# B135X.net
KiCad netlist of a schematic drawn in EAGLE
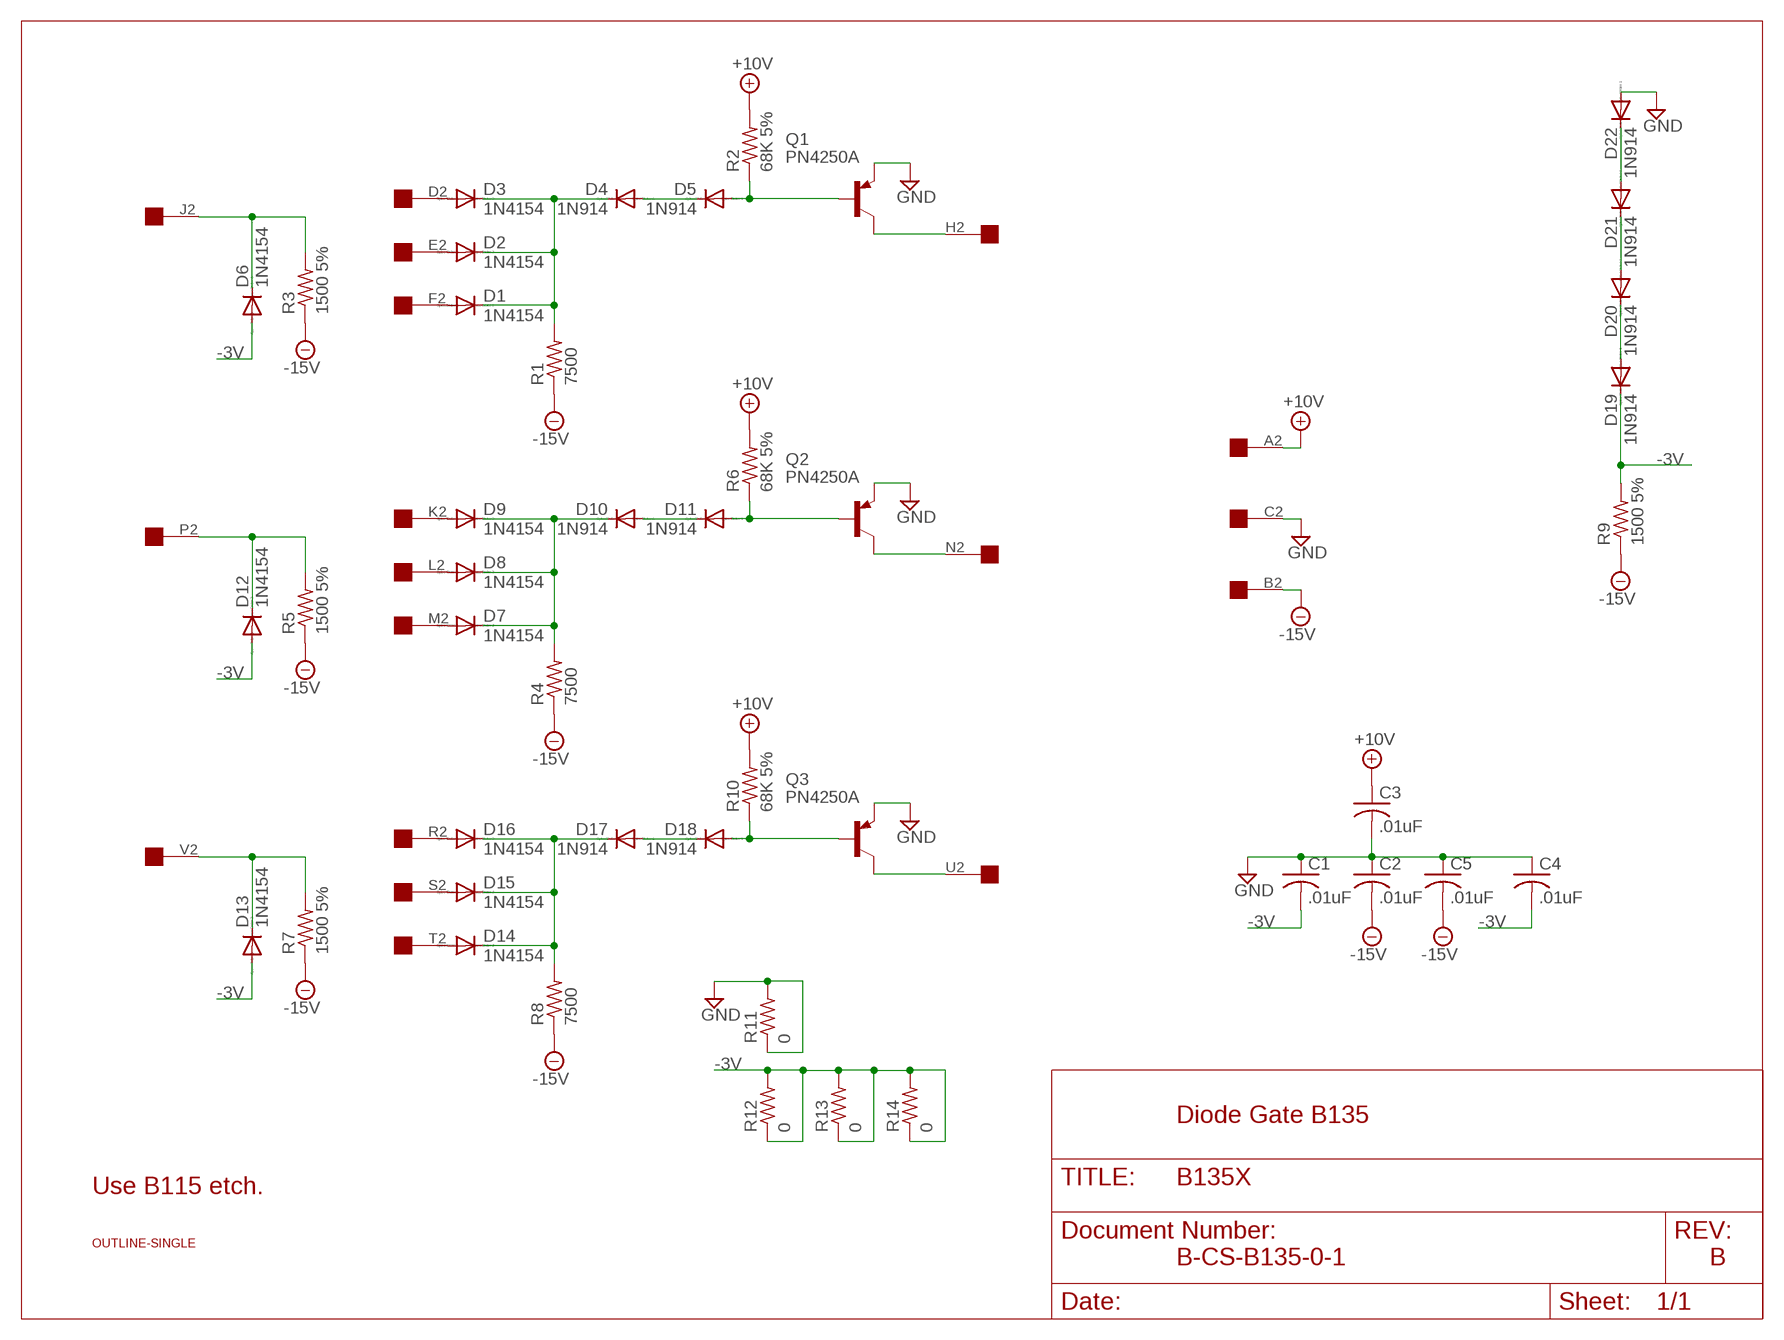
[diagram p0: schematic, sheet 1]

(export (version "E")
  (design (tool "Eeschema 10.0.6"))
  (components
    (comp (ref "C1")
      (value ".01uF")
      (footprint "eagle-import:C063-025X075")
      (libsource (lib "eagle-import") (part "C-US"))
    )
    (comp (ref "C2")
      (value ".01uF")
      (footprint "eagle-import:C063-025X075")
      (libsource (lib "eagle-import") (part "C-US"))
    )
    (comp (ref "C3")
      (value ".01uF")
      (footprint "eagle-import:C063-025X075")
      (libsource (lib "eagle-import") (part "C-US"))
    )
    (comp (ref "C4")
      (value ".01uF")
      (footprint "eagle-import:C063-025X075")
      (libsource (lib "eagle-import") (part "C-US"))
    )
    (comp (ref "C5")
      (value ".01uF")
      (footprint "eagle-import:C063-025X075")
      (libsource (lib "eagle-import") (part "C-US"))
    )
    (comp (ref "D1")
      (value "1N4154")
      (footprint "eagle-import:DO35-10")
      (libsource (lib "eagle-import") (part "DIODE-DO35-10"))
    )
    (comp (ref "D2")
      (value "1N4154")
      (footprint "eagle-import:DO35-10")
      (libsource (lib "eagle-import") (part "DIODE-DO35-10"))
    )
    (comp (ref "D3")
      (value "1N4154")
      (footprint "eagle-import:DO35-10")
      (libsource (lib "eagle-import") (part "DIODE-DO35-10"))
    )
    (comp (ref "D4")
      (value "1N914")
      (footprint "eagle-import:DO35-10")
      (libsource (lib "eagle-import") (part "DIODE-DO35-10"))
    )
    (comp (ref "D5")
      (value "1N914")
      (footprint "eagle-import:DO35-10")
      (libsource (lib "eagle-import") (part "DIODE-DO35-10"))
    )
    (comp (ref "D6")
      (value "1N4154")
      (footprint "eagle-import:DO35-10")
      (libsource (lib "eagle-import") (part "DIODE-DO35-10"))
    )
    (comp (ref "D7")
      (value "1N4154")
      (footprint "eagle-import:DO35-10")
      (libsource (lib "eagle-import") (part "DIODE-DO35-10"))
    )
    (comp (ref "D8")
      (value "1N4154")
      (footprint "eagle-import:DO35-10")
      (libsource (lib "eagle-import") (part "DIODE-DO35-10"))
    )
    (comp (ref "D9")
      (value "1N4154")
      (footprint "eagle-import:DO35-10")
      (libsource (lib "eagle-import") (part "DIODE-DO35-10"))
    )
    (comp (ref "D10")
      (value "1N914")
      (footprint "eagle-import:DO35-10")
      (libsource (lib "eagle-import") (part "DIODE-DO35-10"))
    )
    (comp (ref "D11")
      (value "1N914")
      (footprint "eagle-import:DO35-10")
      (libsource (lib "eagle-import") (part "DIODE-DO35-10"))
    )
    (comp (ref "D12")
      (value "1N4154")
      (footprint "eagle-import:DO35-10")
      (libsource (lib "eagle-import") (part "DIODE-DO35-10"))
    )
    (comp (ref "D13")
      (value "1N4154")
      (footprint "eagle-import:DO35-10")
      (libsource (lib "eagle-import") (part "DIODE-DO35-10"))
    )
    (comp (ref "D14")
      (value "1N4154")
      (footprint "eagle-import:DO35-10")
      (libsource (lib "eagle-import") (part "DIODE-DO35-10"))
    )
    (comp (ref "D15")
      (value "1N4154")
      (footprint "eagle-import:DO35-10")
      (libsource (lib "eagle-import") (part "DIODE-DO35-10"))
    )
    (comp (ref "D16")
      (value "1N4154")
      (footprint "eagle-import:DO35-10")
      (libsource (lib "eagle-import") (part "DIODE-DO35-10"))
    )
    (comp (ref "D17")
      (value "1N914")
      (footprint "eagle-import:DO35-10")
      (libsource (lib "eagle-import") (part "DIODE-DO35-10"))
    )
    (comp (ref "D18")
      (value "1N914")
      (footprint "eagle-import:DO35-10")
      (libsource (lib "eagle-import") (part "DIODE-DO35-10"))
    )
    (comp (ref "D19")
      (value "1N914")
      (footprint "eagle-import:DO35-10")
      (libsource (lib "eagle-import") (part "DIODE-DO35-10"))
    )
    (comp (ref "D20")
      (value "1N914")
      (footprint "eagle-import:DO35-10")
      (libsource (lib "eagle-import") (part "DIODE-DO35-10"))
    )
    (comp (ref "D21")
      (value "1N914")
      (footprint "eagle-import:DO35-10")
      (libsource (lib "eagle-import") (part "DIODE-DO35-10"))
    )
    (comp (ref "D22")
      (value "1N914")
      (footprint "eagle-import:DO35-10")
      (libsource (lib "eagle-import") (part "DIODE-DO35-10"))
    )
    (comp (ref "Q1")
      (value "PN4250A")
      (footprint "eagle-import:TO5")
      (libsource (lib "eagle-import") (part "-PNP-TO5"))
    )
    (comp (ref "Q2")
      (value "PN4250A")
      (footprint "eagle-import:TO5")
      (libsource (lib "eagle-import") (part "-PNP-TO5"))
    )
    (comp (ref "Q3")
      (value "PN4250A")
      (footprint "eagle-import:TO5")
      (libsource (lib "eagle-import") (part "-PNP-TO5"))
    )
    (comp (ref "R1")
      (value "7500")
      (footprint "eagle-import:0207_10")
      (libsource (lib "eagle-import") (part "R-US_0207/10"))
    )
    (comp (ref "R2")
      (value "68K 5%")
      (footprint "eagle-import:0207_10")
      (libsource (lib "eagle-import") (part "R-US_0207/10"))
    )
    (comp (ref "R3")
      (value "1500 5%")
      (footprint "eagle-import:0207_10")
      (libsource (lib "eagle-import") (part "R-US_0207/10"))
    )
    (comp (ref "R4")
      (value "7500")
      (footprint "eagle-import:0207_10")
      (libsource (lib "eagle-import") (part "R-US_0207/10"))
    )
    (comp (ref "R5")
      (value "1500 5%")
      (footprint "eagle-import:0207_10")
      (libsource (lib "eagle-import") (part "R-US_0207/10"))
    )
    (comp (ref "R6")
      (value "68K 5%")
      (footprint "eagle-import:0207_10")
      (libsource (lib "eagle-import") (part "R-US_0207/10"))
    )
    (comp (ref "R7")
      (value "1500 5%")
      (footprint "eagle-import:0207_10")
      (libsource (lib "eagle-import") (part "R-US_0207/10"))
    )
    (comp (ref "R8")
      (value "7500")
      (footprint "eagle-import:0207_10")
      (libsource (lib "eagle-import") (part "R-US_0207/10"))
    )
    (comp (ref "R9")
      (value "1500 5%")
      (footprint "eagle-import:0207_10")
      (libsource (lib "eagle-import") (part "R-US_0207/10"))
    )
    (comp (ref "R10")
      (value "68K 5%")
      (footprint "eagle-import:0207_10")
      (libsource (lib "eagle-import") (part "R-US_0207/10"))
    )
    (comp (ref "R11")
      (value "0")
      (footprint "eagle-import:0207_10")
      (libsource (lib "eagle-import") (part "R-US_0207/10"))
    )
    (comp (ref "R12")
      (value "0")
      (footprint "eagle-import:0207_10")
      (libsource (lib "eagle-import") (part "R-US_0207/10"))
    )
    (comp (ref "R13")
      (value "0")
      (footprint "eagle-import:0207_10")
      (libsource (lib "eagle-import") (part "R-US_0207/10"))
    )
    (comp (ref "R14")
      (value "0")
      (footprint "eagle-import:0207_10")
      (libsource (lib "eagle-import") (part "R-US_0207/10"))
    )
    (comp (ref "U$1")
      (value "OUTLINE-SINGLE")
      (footprint "eagle-import:SINGLE")
      (libsource (lib "eagle-import") (part "OUTLINE-SINGLE"))
    )
    (comp (ref "U$2")
      (value "EDGE-1")
      (footprint "eagle-import:EDGE-CON1")
      (libsource (lib "eagle-import") (part "EDGE-1"))
    )
  )
  (nets
    (net (code "1") (name "+10V") (class "Default")
      (node (ref "C3") (pin "1") (pinfunction "1_1") (pintype "passive"))
      (node (ref "R10") (pin "2") (pinfunction "2_2") (pintype "passive"))
      (node (ref "R2") (pin "2") (pinfunction "2_2") (pintype "passive"))
      (node (ref "R6") (pin "2") (pinfunction "2_2") (pintype "passive"))
      (node (ref "U$2") (pin "A2") (pinfunction "1_A2") (pintype "bidirectional"))
    )
    (net (code "2") (name "-15V") (class "Default")
      (node (ref "C2") (pin "2") (pinfunction "2_2") (pintype "passive"))
      (node (ref "C5") (pin "2") (pinfunction "2_2") (pintype "passive"))
      (node (ref "R1") (pin "1") (pinfunction "1_1") (pintype "passive"))
      (node (ref "R3") (pin "1") (pinfunction "1_1") (pintype "passive"))
      (node (ref "R4") (pin "1") (pinfunction "1_1") (pintype "passive"))
      (node (ref "R5") (pin "1") (pinfunction "1_1") (pintype "passive"))
      (node (ref "R7") (pin "1") (pinfunction "1_1") (pintype "passive"))
      (node (ref "R8") (pin "1") (pinfunction "1_1") (pintype "passive"))
      (node (ref "R9") (pin "1") (pinfunction "1_1") (pintype "passive"))
      (node (ref "U$2") (pin "B2") (pinfunction "1_B2") (pintype "bidirectional"))
    )
    (net (code "3") (name "/-3V") (class "Default")
      (node (ref "C1") (pin "2") (pinfunction "2_2") (pintype "passive"))
      (node (ref "C4") (pin "2") (pinfunction "2_2") (pintype "passive"))
      (node (ref "D12") (pin "A") (pinfunction "A_A") (pintype "passive"))
      (node (ref "D13") (pin "A") (pinfunction "A_A") (pintype "passive"))
      (node (ref "D19") (pin "C") (pinfunction "C_C") (pintype "passive"))
      (node (ref "D6") (pin "A") (pinfunction "A_A") (pintype "passive"))
      (node (ref "R12") (pin "1") (pinfunction "1_1") (pintype "passive"))
      (node (ref "R12") (pin "2") (pinfunction "2_2") (pintype "passive"))
      (node (ref "R13") (pin "1") (pinfunction "1_1") (pintype "passive"))
      (node (ref "R13") (pin "2") (pinfunction "2_2") (pintype "passive"))
      (node (ref "R14") (pin "1") (pinfunction "1_1") (pintype "passive"))
      (node (ref "R14") (pin "2") (pinfunction "2_2") (pintype "passive"))
      (node (ref "R9") (pin "2") (pinfunction "2_2") (pintype "passive"))
    )
    (net (code "4") (name "GND") (class "Default")
      (node (ref "C1") (pin "1") (pinfunction "1_1") (pintype "passive"))
      (node (ref "C2") (pin "1") (pinfunction "1_1") (pintype "passive"))
      (node (ref "C3") (pin "2") (pinfunction "2_2") (pintype "passive"))
      (node (ref "C4") (pin "1") (pinfunction "1_1") (pintype "passive"))
      (node (ref "C5") (pin "1") (pinfunction "1_1") (pintype "passive"))
      (node (ref "D22") (pin "A") (pinfunction "A_A") (pintype "passive"))
      (node (ref "Q1") (pin "1") (pinfunction "E_1") (pintype "passive"))
      (node (ref "Q2") (pin "1") (pinfunction "E_1") (pintype "passive"))
      (node (ref "Q3") (pin "1") (pinfunction "E_1") (pintype "passive"))
      (node (ref "R11") (pin "1") (pinfunction "1_1") (pintype "passive"))
      (node (ref "R11") (pin "2") (pinfunction "2_2") (pintype "passive"))
      (node (ref "U$2") (pin "C2") (pinfunction "1_C2") (pintype "bidirectional"))
    )
    (net (code "5") (name "Net-(D1-PadC)") (class "Default")
      (node (ref "D1") (pin "C") (pinfunction "C_C") (pintype "passive"))
      (node (ref "D2") (pin "C") (pinfunction "C_C") (pintype "passive"))
      (node (ref "D3") (pin "C") (pinfunction "C_C") (pintype "passive"))
      (node (ref "D4") (pin "C") (pinfunction "C_C") (pintype "passive"))
      (node (ref "R1") (pin "2") (pinfunction "2_2") (pintype "passive"))
    )
    (net (code "6") (name "Net-(D4-PadA)") (class "Default")
      (node (ref "D4") (pin "A") (pinfunction "A_A") (pintype "passive"))
      (node (ref "D5") (pin "C") (pinfunction "C_C") (pintype "passive"))
    )
    (net (code "7") (name "Net-(D10-PadA)") (class "Default")
      (node (ref "D10") (pin "A") (pinfunction "A_A") (pintype "passive"))
      (node (ref "D11") (pin "C") (pinfunction "C_C") (pintype "passive"))
    )
    (net (code "8") (name "Net-(D10-PadC)") (class "Default")
      (node (ref "D10") (pin "C") (pinfunction "C_C") (pintype "passive"))
      (node (ref "D7") (pin "C") (pinfunction "C_C") (pintype "passive"))
      (node (ref "D8") (pin "C") (pinfunction "C_C") (pintype "passive"))
      (node (ref "D9") (pin "C") (pinfunction "C_C") (pintype "passive"))
      (node (ref "R4") (pin "2") (pinfunction "2_2") (pintype "passive"))
    )
    (net (code "9") (name "Net-(D14-PadC)") (class "Default")
      (node (ref "D14") (pin "C") (pinfunction "C_C") (pintype "passive"))
      (node (ref "D15") (pin "C") (pinfunction "C_C") (pintype "passive"))
      (node (ref "D16") (pin "C") (pinfunction "C_C") (pintype "passive"))
      (node (ref "D17") (pin "C") (pinfunction "C_C") (pintype "passive"))
      (node (ref "R8") (pin "2") (pinfunction "2_2") (pintype "passive"))
    )
    (net (code "10") (name "Net-(D17-PadA)") (class "Default")
      (node (ref "D17") (pin "A") (pinfunction "A_A") (pintype "passive"))
      (node (ref "D18") (pin "C") (pinfunction "C_C") (pintype "passive"))
    )
    (net (code "11") (name "Net-(D19-PadA)") (class "Default")
      (node (ref "D19") (pin "A") (pinfunction "A_A") (pintype "passive"))
      (node (ref "D20") (pin "C") (pinfunction "C_C") (pintype "passive"))
    )
    (net (code "12") (name "Net-(D20-PadA)") (class "Default")
      (node (ref "D20") (pin "A") (pinfunction "A_A") (pintype "passive"))
      (node (ref "D21") (pin "C") (pinfunction "C_C") (pintype "passive"))
    )
    (net (code "13") (name "Net-(D21-PadA)") (class "Default")
      (node (ref "D21") (pin "A") (pinfunction "A_A") (pintype "passive"))
      (node (ref "D22") (pin "C") (pinfunction "C_C") (pintype "passive"))
    )
    (net (code "14") (name "Net-(Q1-B)") (class "Default")
      (node (ref "D5") (pin "A") (pinfunction "A_A") (pintype "passive"))
      (node (ref "Q1") (pin "2") (pinfunction "B_2") (pintype "passive"))
      (node (ref "R2") (pin "1") (pinfunction "1_1") (pintype "passive"))
    )
    (net (code "15") (name "Net-(Q1-C)") (class "Default")
      (node (ref "Q1") (pin "3") (pinfunction "C_3") (pintype "passive"))
      (node (ref "U$2") (pin "H2") (pinfunction "1_H2") (pintype "bidirectional"))
    )
    (net (code "16") (name "Net-(Q2-B)") (class "Default")
      (node (ref "D11") (pin "A") (pinfunction "A_A") (pintype "passive"))
      (node (ref "Q2") (pin "2") (pinfunction "B_2") (pintype "passive"))
      (node (ref "R6") (pin "1") (pinfunction "1_1") (pintype "passive"))
    )
    (net (code "17") (name "Net-(Q2-C)") (class "Default")
      (node (ref "Q2") (pin "3") (pinfunction "C_3") (pintype "passive"))
      (node (ref "U$2") (pin "N2") (pinfunction "1_N2") (pintype "bidirectional"))
    )
    (net (code "18") (name "Net-(Q3-B)") (class "Default")
      (node (ref "D18") (pin "A") (pinfunction "A_A") (pintype "passive"))
      (node (ref "Q3") (pin "2") (pinfunction "B_2") (pintype "passive"))
      (node (ref "R10") (pin "1") (pinfunction "1_1") (pintype "passive"))
    )
    (net (code "19") (name "Net-(Q3-C)") (class "Default")
      (node (ref "Q3") (pin "3") (pinfunction "C_3") (pintype "passive"))
      (node (ref "U$2") (pin "U2") (pinfunction "1_U2") (pintype "bidirectional"))
    )
    (net (code "20") (name "Net-(U$2D-1)") (class "Default")
      (node (ref "D3") (pin "A") (pinfunction "A_A") (pintype "passive"))
      (node (ref "U$2") (pin "D2") (pinfunction "1_D2") (pintype "bidirectional"))
    )
    (net (code "21") (name "Net-(U$2E-1)") (class "Default")
      (node (ref "D2") (pin "A") (pinfunction "A_A") (pintype "passive"))
      (node (ref "U$2") (pin "E2") (pinfunction "1_E2") (pintype "bidirectional"))
    )
    (net (code "22") (name "Net-(U$2F-1)") (class "Default")
      (node (ref "D1") (pin "A") (pinfunction "A_A") (pintype "passive"))
      (node (ref "U$2") (pin "F2") (pinfunction "1_F2") (pintype "bidirectional"))
    )
    (net (code "23") (name "Net-(U$2H-1)") (class "Default")
      (node (ref "D6") (pin "C") (pinfunction "C_C") (pintype "passive"))
      (node (ref "R3") (pin "2") (pinfunction "2_2") (pintype "passive"))
      (node (ref "U$2") (pin "J2") (pinfunction "1_J2") (pintype "bidirectional"))
    )
    (net (code "24") (name "Net-(U$2I-1)") (class "Default")
      (node (ref "D9") (pin "A") (pinfunction "A_A") (pintype "passive"))
      (node (ref "U$2") (pin "K2") (pinfunction "1_K2") (pintype "bidirectional"))
    )
    (net (code "25") (name "Net-(U$2J-1)") (class "Default")
      (node (ref "D8") (pin "A") (pinfunction "A_A") (pintype "passive"))
      (node (ref "U$2") (pin "L2") (pinfunction "1_L2") (pintype "bidirectional"))
    )
    (net (code "26") (name "Net-(U$2K-1)") (class "Default")
      (node (ref "D7") (pin "A") (pinfunction "A_A") (pintype "passive"))
      (node (ref "U$2") (pin "M2") (pinfunction "1_M2") (pintype "bidirectional"))
    )
    (net (code "27") (name "Net-(U$2M-1)") (class "Default")
      (node (ref "D12") (pin "C") (pinfunction "C_C") (pintype "passive"))
      (node (ref "R5") (pin "2") (pinfunction "2_2") (pintype "passive"))
      (node (ref "U$2") (pin "P2") (pinfunction "1_P2") (pintype "bidirectional"))
    )
    (net (code "28") (name "Net-(U$2N-1)") (class "Default")
      (node (ref "D16") (pin "A") (pinfunction "A_A") (pintype "passive"))
      (node (ref "U$2") (pin "R2") (pinfunction "1_R2") (pintype "bidirectional"))
    )
    (net (code "29") (name "Net-(U$2O-1)") (class "Default")
      (node (ref "D15") (pin "A") (pinfunction "A_A") (pintype "passive"))
      (node (ref "U$2") (pin "S2") (pinfunction "1_S2") (pintype "bidirectional"))
    )
    (net (code "30") (name "Net-(U$2P-1)") (class "Default")
      (node (ref "D14") (pin "A") (pinfunction "A_A") (pintype "passive"))
      (node (ref "U$2") (pin "T2") (pinfunction "1_T2") (pintype "bidirectional"))
    )
    (net (code "31") (name "Net-(U$2R-1)") (class "Default")
      (node (ref "D13") (pin "C") (pinfunction "C_C") (pintype "passive"))
      (node (ref "R7") (pin "2") (pinfunction "2_2") (pintype "passive"))
      (node (ref "U$2") (pin "V2") (pinfunction "1_V2") (pintype "bidirectional"))
    )
  )
)
